# tiny-dcdc.net
KiCad netlist of a schematic drawn in EAGLE
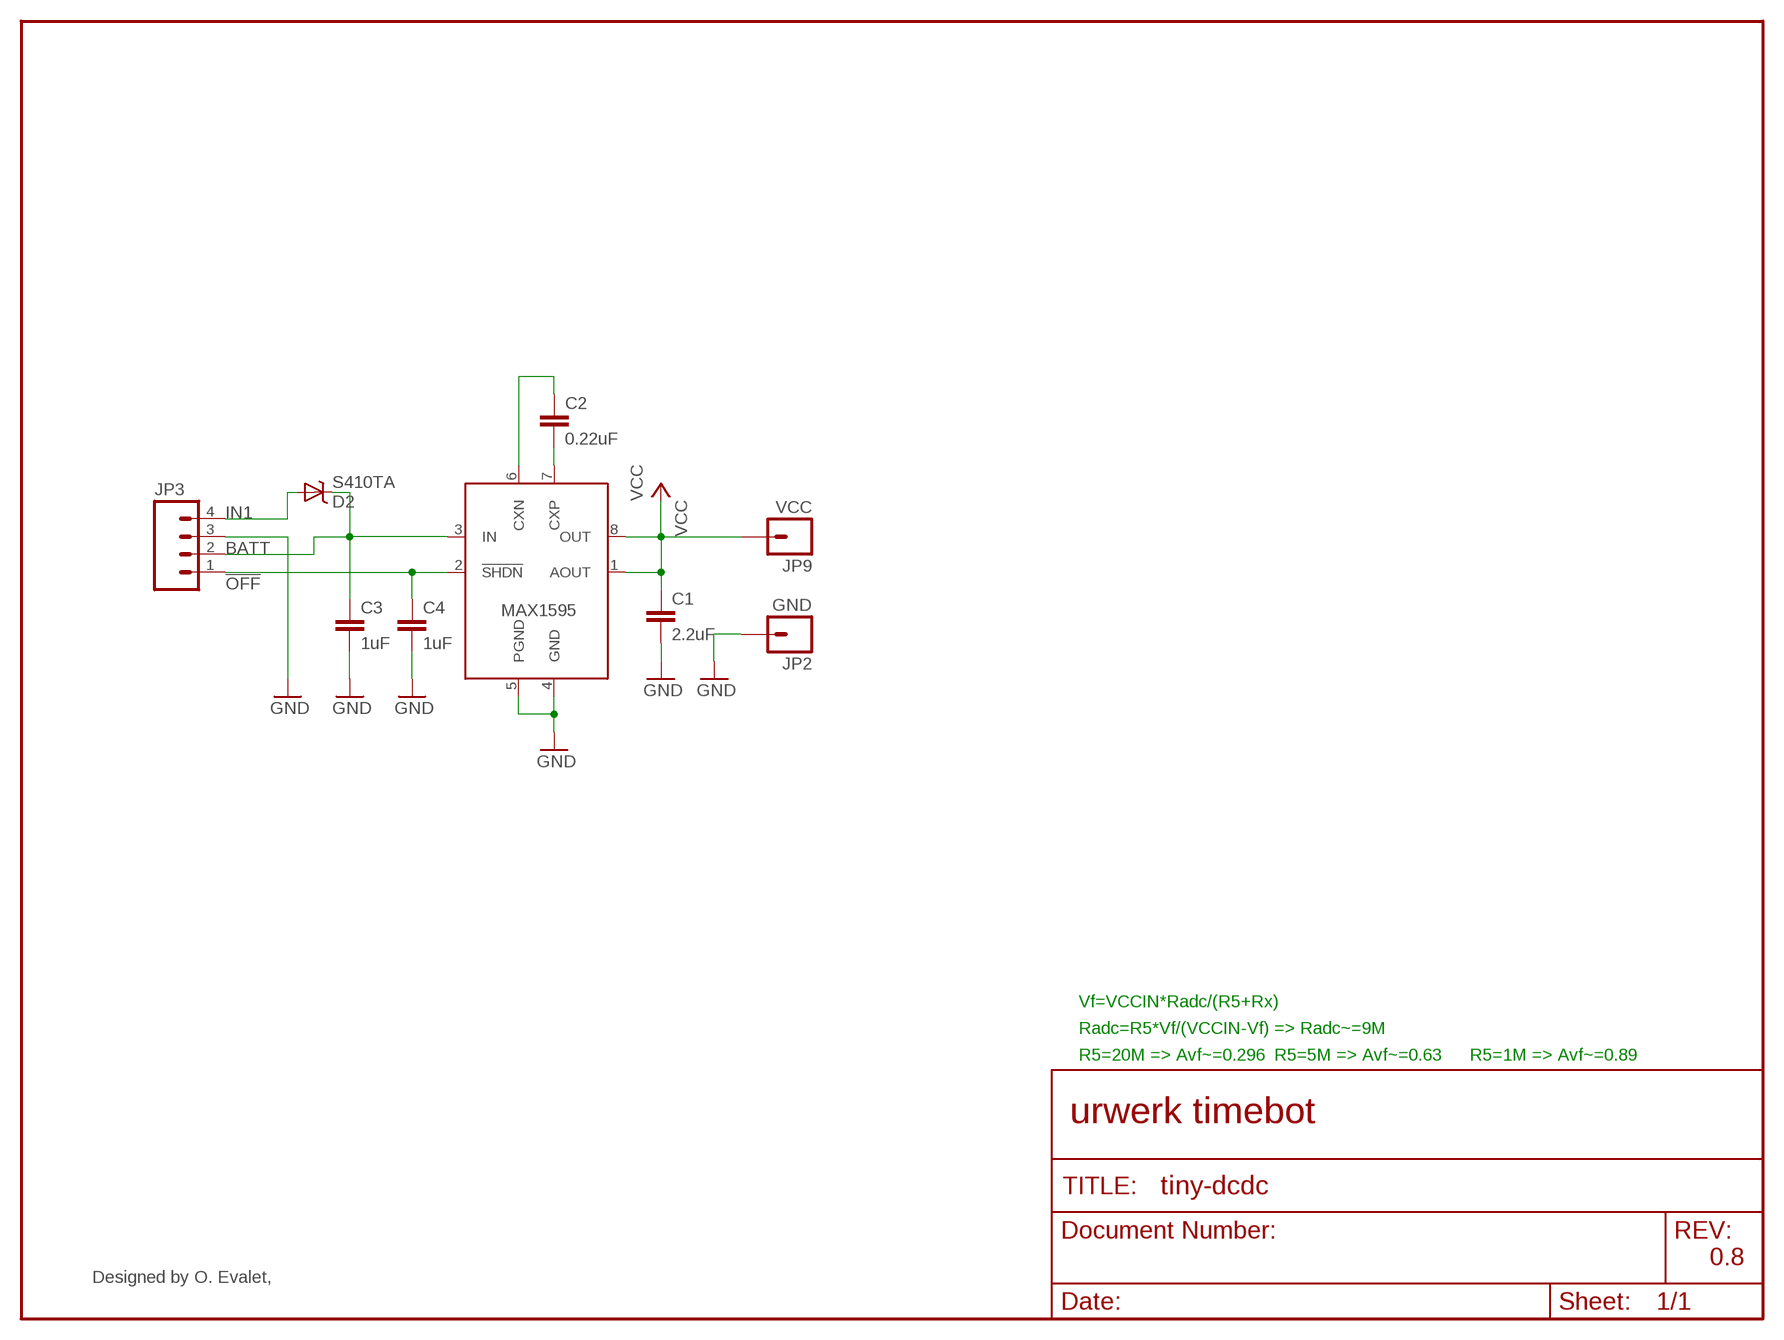
[diagram p0: schematic, sheet 1]

(export (version "E")
  (design (tool "Eeschema 10.0.6"))
  (components
    (comp (ref "C1")
      (value "2.2uF")
      (footprint "eagle-import:0805")
      (libsource (lib "eagle-import") (part "CAP0805"))
    )
    (comp (ref "C2")
      (value "0.22uF")
      (footprint "eagle-import:0805")
      (libsource (lib "eagle-import") (part "CAP0805"))
    )
    (comp (ref "C3")
      (value "1uF")
      (footprint "eagle-import:0805")
      (libsource (lib "eagle-import") (part "CAP0805"))
    )
    (comp (ref "C4")
      (value "1uF")
      (footprint "eagle-import:0805")
      (libsource (lib "eagle-import") (part "CAP0805"))
    )
    (comp (ref "D2")
      (value "S410TA")
      (footprint "eagle-import:SOD-323")
      (libsource (lib "eagle-import") (part "DIODE-SCHOTTKY"))
    )
    (comp (ref "JP2")
      (value "GND")
      (footprint "eagle-import:URWERK1X01")
      (libsource (lib "eagle-import") (part "M01URWERK-ROUND"))
    )
    (comp (ref "JP3")
      (value "M041.27MM")
      (footprint "eagle-import:1X04-1.27MM")
      (libsource (lib "eagle-import") (part "M041.27MM"))
    )
    (comp (ref "JP9")
      (value "VCC")
      (footprint "eagle-import:URWERK1-SMALLX01")
      (libsource (lib "eagle-import") (part "M01SMALL"))
    )
    (comp (ref "U$1")
      (value "MAX1595")
      (footprint "eagle-import:UMAX8")
      (libsource (lib "eagle-import") (part "MAX1595"))
    )
  )
  (nets
    (net (code "1") (name "/BATT") (class "Default")
      (node (ref "C3") (pin "1") (pinfunction "1_1") (pintype "passive"))
      (node (ref "D2") (pin "1") (pinfunction "C_1") (pintype "passive"))
      (node (ref "JP3") (pin "2") (pinfunction "2_2") (pintype "passive"))
      (node (ref "U$1") (pin "3") (pinfunction "IN_3") (pintype "input"))
    )
    (net (code "2") (name "/IN1") (class "Default")
      (node (ref "D2") (pin "2") (pinfunction "A_2") (pintype "passive"))
      (node (ref "JP3") (pin "4") (pinfunction "4_4") (pintype "passive"))
    )
    (net (code "3") (name "/~{OFF}") (class "Default")
      (node (ref "C4") (pin "1") (pinfunction "1_1") (pintype "passive"))
      (node (ref "JP3") (pin "1") (pinfunction "1_1") (pintype "passive"))
      (node (ref "U$1") (pin "2") (pinfunction "~{SHDN}_2") (pintype "input"))
    )
    (net (code "4") (name "GND") (class "Default")
      (node (ref "C1") (pin "2") (pinfunction "2_2") (pintype "passive"))
      (node (ref "C3") (pin "2") (pinfunction "2_2") (pintype "passive"))
      (node (ref "C4") (pin "2") (pinfunction "2_2") (pintype "passive"))
      (node (ref "JP2") (pin "1") (pinfunction "1_1") (pintype "passive"))
      (node (ref "JP3") (pin "3") (pinfunction "3_3") (pintype "passive"))
      (node (ref "U$1") (pin "4") (pinfunction "GND_4") (pintype "power_in"))
      (node (ref "U$1") (pin "5") (pinfunction "PGND_5") (pintype "power_in"))
    )
    (net (code "5") (name "Net-(U$1-CXN)") (class "Default")
      (node (ref "C2") (pin "1") (pinfunction "1_1") (pintype "passive"))
      (node (ref "U$1") (pin "6") (pinfunction "CXN_6") (pintype "passive"))
    )
    (net (code "6") (name "Net-(U$1-CXP)") (class "Default")
      (node (ref "C2") (pin "2") (pinfunction "2_2") (pintype "passive"))
      (node (ref "U$1") (pin "7") (pinfunction "CXP_7") (pintype "passive"))
    )
    (net (code "7") (name "VCC") (class "Default")
      (node (ref "C1") (pin "1") (pinfunction "1_1") (pintype "passive"))
      (node (ref "JP9") (pin "1") (pinfunction "1_1") (pintype "passive"))
      (node (ref "U$1") (pin "1") (pinfunction "AOUT_1") (pintype "passive"))
      (node (ref "U$1") (pin "8") (pinfunction "OUT_8") (pintype "passive"))
    )
  )
)
